# USBJTAG_USBUART_4-Channel.net
KiCad netlist of a schematic drawn in Altium Designer
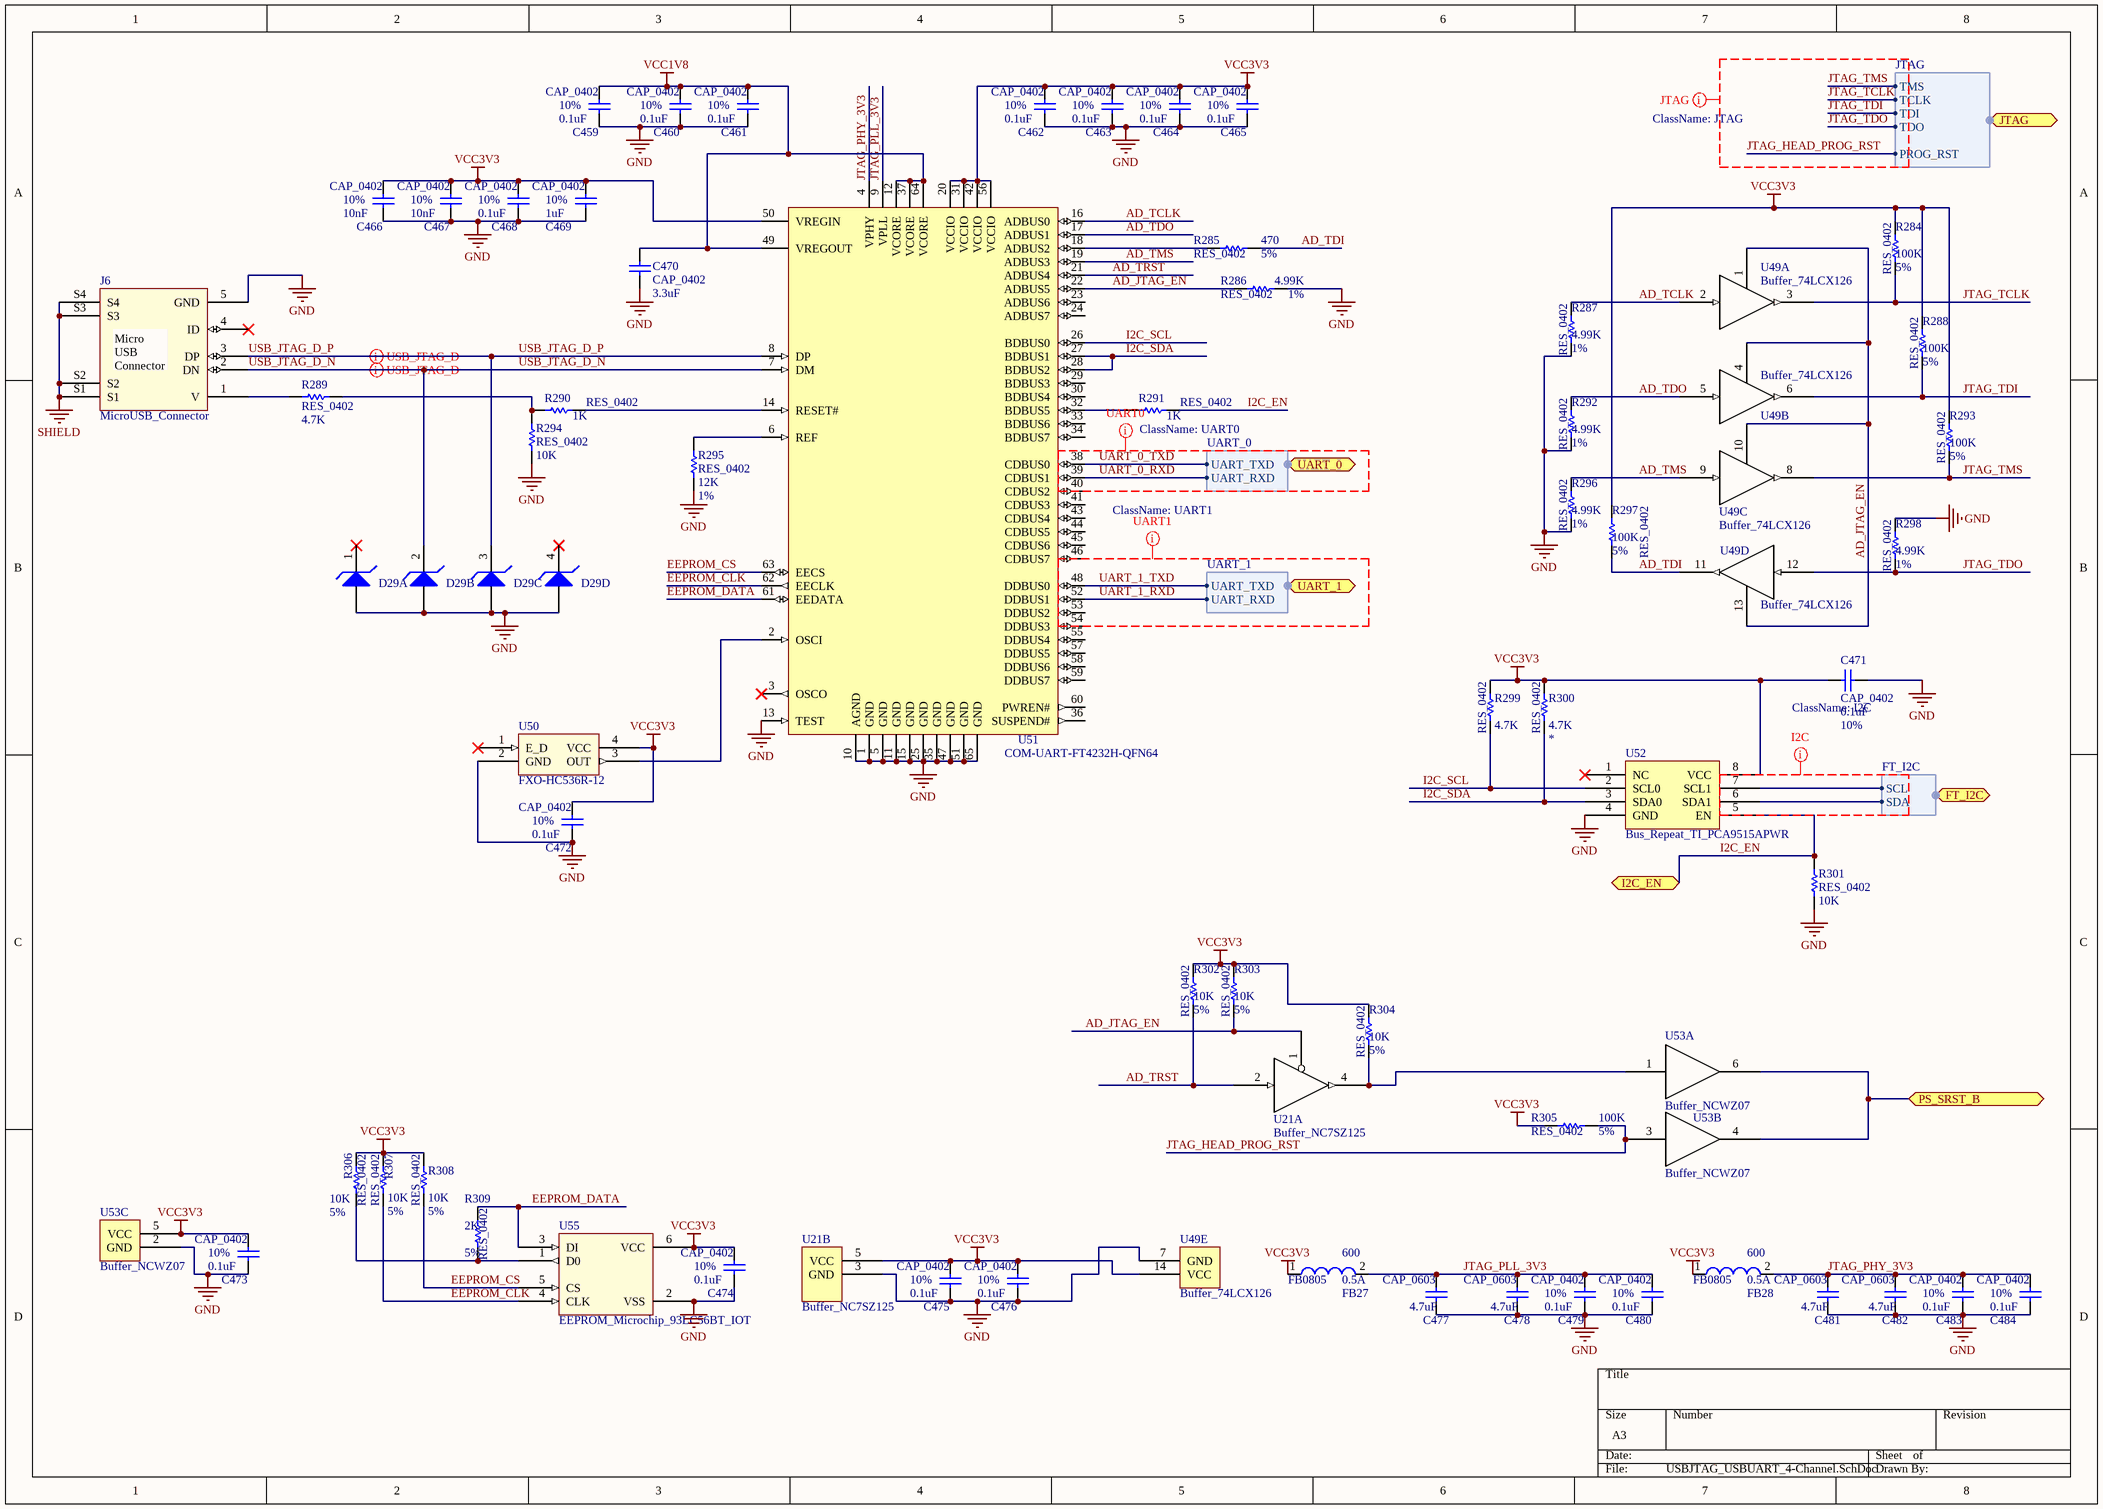
[diagram p0: USBJTAG_USBUART_4-Channel.SchDoc]

(export (version "E")
  (design (tool "Eeschema 10.0.6"))
  (components
    (comp (ref "C459")
      (value "CAP_0402")
      (footprint "CAPC0402(1005)60_N:CAPC0402(1005)60_N")
      (description "0.1uf, ceramic, 10%, 6.3V, X5R, 0402")
      (fields
        (field (name "ALTIUM_VALUE") "0.1uF")
        (field (name "TOLERANCE") "10%")
        (field (name "PART NUMBER") "C1005X5R0J104K")
        (field (name "MANUFACTURER") "TDK Corporation")
      )
      (libsource (lib "COMRAD_Database") (part "CAP_0402"))
    )
    (comp (ref "C460")
      (value "CAP_0402")
      (footprint "CAPC0402(1005)60_N:CAPC0402(1005)60_N")
      (description "0.1uf, ceramic, 10%, 6.3V, X5R, 0402")
      (fields
        (field (name "ALTIUM_VALUE") "0.1uF")
        (field (name "TOLERANCE") "10%")
        (field (name "PART NUMBER") "C1005X5R0J104K")
        (field (name "MANUFACTURER") "TDK Corporation")
      )
      (libsource (lib "COMRAD_Database") (part "CAP_0402"))
    )
    (comp (ref "C461")
      (value "CAP_0402")
      (footprint "CAPC0402(1005)60_N:CAPC0402(1005)60_N")
      (description "0.1uf, ceramic, 10%, 6.3V, X5R, 0402")
      (fields
        (field (name "ALTIUM_VALUE") "0.1uF")
        (field (name "TOLERANCE") "10%")
        (field (name "PART NUMBER") "C1005X5R0J104K")
        (field (name "MANUFACTURER") "TDK Corporation")
      )
      (libsource (lib "COMRAD_Database") (part "CAP_0402"))
    )
    (comp (ref "C462")
      (value "CAP_0402")
      (footprint "CAPC0402(1005)60_N:CAPC0402(1005)60_N")
      (description "0.1uf, ceramic, 10%, 6.3V, X5R, 0402")
      (fields
        (field (name "ALTIUM_VALUE") "0.1uF")
        (field (name "TOLERANCE") "10%")
        (field (name "PART NUMBER") "C1005X5R0J104K")
        (field (name "MANUFACTURER") "TDK Corporation")
      )
      (libsource (lib "COMRAD_Database") (part "CAP_0402"))
    )
    (comp (ref "C463")
      (value "CAP_0402")
      (footprint "CAPC0402(1005)60_N:CAPC0402(1005)60_N")
      (description "0.1uf, ceramic, 10%, 6.3V, X5R, 0402")
      (fields
        (field (name "ALTIUM_VALUE") "0.1uF")
        (field (name "TOLERANCE") "10%")
        (field (name "PART NUMBER") "C1005X5R0J104K")
        (field (name "MANUFACTURER") "TDK Corporation")
      )
      (libsource (lib "COMRAD_Database") (part "CAP_0402"))
    )
    (comp (ref "C464")
      (value "CAP_0402")
      (footprint "CAPC0402(1005)60_N:CAPC0402(1005)60_N")
      (description "0.1uf, ceramic, 10%, 6.3V, X5R, 0402")
      (fields
        (field (name "ALTIUM_VALUE") "0.1uF")
        (field (name "TOLERANCE") "10%")
        (field (name "PART NUMBER") "C1005X5R0J104K")
        (field (name "MANUFACTURER") "TDK Corporation")
      )
      (libsource (lib "COMRAD_Database") (part "CAP_0402"))
    )
    (comp (ref "C465")
      (value "CAP_0402")
      (footprint "CAPC0402(1005)60_N:CAPC0402(1005)60_N")
      (description "0.1uf, ceramic, 10%, 6.3V, X5R, 0402")
      (fields
        (field (name "ALTIUM_VALUE") "0.1uF")
        (field (name "TOLERANCE") "10%")
        (field (name "PART NUMBER") "C1005X5R0J104K")
        (field (name "MANUFACTURER") "TDK Corporation")
      )
      (libsource (lib "COMRAD_Database") (part "CAP_0402"))
    )
    (comp (ref "C466")
      (value "CAP_0402")
      (footprint "CAPC0402(1005)60_N:CAPC0402(1005)60_N")
      (description "10000pF, ceramic, 10% 6.3V X5R, 0402")
      (fields
        (field (name "ALTIUM_VALUE") "10nF")
        (field (name "TOLERANCE") "10%")
        (field (name "PART NUMBER") "GRM155R60J103KA01D")
        (field (name "MANUFACTURER") "Murata Electronics North America")
      )
      (libsource (lib "COMRAD_Database") (part "CAP_0402"))
    )
    (comp (ref "C467")
      (value "CAP_0402")
      (footprint "CAPC0402(1005)60_N:CAPC0402(1005)60_N")
      (description "10000pF, ceramic, 10% 6.3V X5R, 0402")
      (fields
        (field (name "ALTIUM_VALUE") "10nF")
        (field (name "TOLERANCE") "10%")
        (field (name "PART NUMBER") "GRM155R60J103KA01D")
        (field (name "MANUFACTURER") "Murata Electronics North America")
      )
      (libsource (lib "COMRAD_Database") (part "CAP_0402"))
    )
    (comp (ref "C468")
      (value "CAP_0402")
      (footprint "CAPC0402(1005)60_N:CAPC0402(1005)60_N")
      (description "0.1uf, ceramic, 10%, 6.3V, X5R, 0402")
      (fields
        (field (name "ALTIUM_VALUE") "0.1uF")
        (field (name "TOLERANCE") "10%")
        (field (name "PART NUMBER") "C1005X5R0J104K")
        (field (name "MANUFACTURER") "TDK Corporation")
      )
      (libsource (lib "COMRAD_Database") (part "CAP_0402"))
    )
    (comp (ref "C469")
      (value "CAP_0402")
      (footprint "CAPC0402(1005)60_N:CAPC0402(1005)60_N")
      (description "1uF, ceramic, 10%, 6.3V, X5R, 0402")
      (fields
        (field (name "ALTIUM_VALUE") "1uF")
        (field (name "TOLERANCE") "10%")
        (field (name "PART NUMBER") "C1005X5R0J105K")
        (field (name "MANUFACTURER") "TDK Corporation")
      )
      (libsource (lib "COMRAD_Database") (part "CAP_0402"))
    )
    (comp (ref "C470")
      (value "CAP_0402")
      (footprint "CAPC0402(1005)60_N")
      (description "CAP CER 3.3UF 6.3V 20% X5R 0402")
      (fields
        (field (name "ALTIUM_VALUE") "3.3uF")
        (field (name "TOLERANCE") "20%")
        (field (name "PART NUMBER") "C1005X5R0J335M050BC")
      )
      (libsource (lib "COMRAD_Database") (part "CAP_0402"))
    )
    (comp (ref "C471")
      (value "CAP_0402")
      (footprint "CAPC0402(1005)60_N:CAPC0402(1005)60_N")
      (description "0.1uf, ceramic, 10%, 6.3V, X5R, 0402")
      (fields
        (field (name "ALTIUM_VALUE") "0.1uF")
        (field (name "TOLERANCE") "10%")
        (field (name "PART NUMBER") "C1005X5R0J104K")
        (field (name "MANUFACTURER") "TDK Corporation")
      )
      (libsource (lib "COMRAD_Database") (part "CAP_0402"))
    )
    (comp (ref "C472")
      (value "CAP_0402")
      (footprint "CAPC0402(1005)60_N:CAPC0402(1005)60_N")
      (description "0.1uf, ceramic, 10%, 6.3V, X5R, 0402")
      (fields
        (field (name "ALTIUM_VALUE") "0.1uF")
        (field (name "TOLERANCE") "10%")
        (field (name "PART NUMBER") "C1005X5R0J104K")
        (field (name "MANUFACTURER") "TDK Corporation")
      )
      (libsource (lib "COMRAD_Database") (part "CAP_0402"))
    )
    (comp (ref "C473")
      (value "CAP_0402")
      (footprint "CAPC0402(1005)60_N:CAPC0402(1005)60_N")
      (description "0.1uf, ceramic, 10%, 6.3V, X5R, 0402")
      (fields
        (field (name "ALTIUM_VALUE") "0.1uF")
        (field (name "TOLERANCE") "10%")
        (field (name "PART NUMBER") "C1005X5R0J104K")
        (field (name "MANUFACTURER") "TDK Corporation")
      )
      (libsource (lib "COMRAD_Database") (part "CAP_0402"))
    )
    (comp (ref "C474")
      (value "CAP_0402")
      (footprint "CAPC0402(1005)60_N:CAPC0402(1005)60_N")
      (description "0.1uf, ceramic, 10%, 6.3V, X5R, 0402")
      (fields
        (field (name "ALTIUM_VALUE") "0.1uF")
        (field (name "TOLERANCE") "10%")
        (field (name "PART NUMBER") "C1005X5R0J104K")
        (field (name "MANUFACTURER") "TDK Corporation")
      )
      (libsource (lib "COMRAD_Database") (part "CAP_0402"))
    )
    (comp (ref "C475")
      (value "CAP_0402")
      (footprint "CAPC0402(1005)60_N:CAPC0402(1005)60_N")
      (description "0.1uf, ceramic, 10%, 6.3V, X5R, 0402")
      (fields
        (field (name "ALTIUM_VALUE") "0.1uF")
        (field (name "TOLERANCE") "10%")
        (field (name "PART NUMBER") "C1005X5R0J104K")
        (field (name "MANUFACTURER") "TDK Corporation")
      )
      (libsource (lib "COMRAD_Database") (part "CAP_0402"))
    )
    (comp (ref "C476")
      (value "CAP_0402")
      (footprint "CAPC0402(1005)60_N:CAPC0402(1005)60_N")
      (description "0.1uf, ceramic, 10%, 6.3V, X5R, 0402")
      (fields
        (field (name "ALTIUM_VALUE") "0.1uF")
        (field (name "TOLERANCE") "10%")
        (field (name "PART NUMBER") "C1005X5R0J104K")
        (field (name "MANUFACTURER") "TDK Corporation")
      )
      (libsource (lib "COMRAD_Database") (part "CAP_0402"))
    )
    (comp (ref "C477")
      (value "CAP_0603")
      (footprint "CAPC0603(1608)100_N")
      (description "4.7uF, ceramic, 10%, 10V X5R, 0603")
      (fields
        (field (name "ALTIUM_VALUE") "4.7uF")
        (field (name "TOLERANCE") "10%")
        (field (name "PART NUMBER") "LMK107BJ475KA-T")
      )
      (libsource (lib "COMRAD_Database") (part "CAP_0603"))
    )
    (comp (ref "C478")
      (value "CAP_0603")
      (footprint "CAPC0603(1608)100_N")
      (description "4.7uF, ceramic, 10%, 10V X5R, 0603")
      (fields
        (field (name "ALTIUM_VALUE") "4.7uF")
        (field (name "TOLERANCE") "10%")
        (field (name "PART NUMBER") "LMK107BJ475KA-T")
      )
      (libsource (lib "COMRAD_Database") (part "CAP_0603"))
    )
    (comp (ref "C479")
      (value "CAP_0402")
      (footprint "CAPC0402(1005)60_N:CAPC0402(1005)60_N")
      (description "0.1uf, ceramic, 10%, 6.3V, X5R, 0402")
      (fields
        (field (name "ALTIUM_VALUE") "0.1uF")
        (field (name "TOLERANCE") "10%")
        (field (name "PART NUMBER") "C1005X5R0J104K")
        (field (name "MANUFACTURER") "TDK Corporation")
      )
      (libsource (lib "COMRAD_Database") (part "CAP_0402"))
    )
    (comp (ref "C480")
      (value "CAP_0402")
      (footprint "CAPC0402(1005)60_N:CAPC0402(1005)60_N")
      (description "0.1uf, ceramic, 10%, 6.3V, X5R, 0402")
      (fields
        (field (name "ALTIUM_VALUE") "0.1uF")
        (field (name "TOLERANCE") "10%")
        (field (name "PART NUMBER") "C1005X5R0J104K")
        (field (name "MANUFACTURER") "TDK Corporation")
      )
      (libsource (lib "COMRAD_Database") (part "CAP_0402"))
    )
    (comp (ref "C481")
      (value "CAP_0603")
      (footprint "CAPC0603(1608)100_N")
      (description "4.7uF, ceramic, 10%, 10V X5R, 0603")
      (fields
        (field (name "ALTIUM_VALUE") "4.7uF")
        (field (name "TOLERANCE") "10%")
        (field (name "PART NUMBER") "LMK107BJ475KA-T")
      )
      (libsource (lib "COMRAD_Database") (part "CAP_0603"))
    )
    (comp (ref "C482")
      (value "CAP_0603")
      (footprint "CAPC0603(1608)100_N")
      (description "4.7uF, ceramic, 10%, 10V X5R, 0603")
      (fields
        (field (name "ALTIUM_VALUE") "4.7uF")
        (field (name "TOLERANCE") "10%")
        (field (name "PART NUMBER") "LMK107BJ475KA-T")
      )
      (libsource (lib "COMRAD_Database") (part "CAP_0603"))
    )
    (comp (ref "C483")
      (value "CAP_0402")
      (footprint "CAPC0402(1005)60_N:CAPC0402(1005)60_N")
      (description "0.1uf, ceramic, 10%, 6.3V, X5R, 0402")
      (fields
        (field (name "ALTIUM_VALUE") "0.1uF")
        (field (name "TOLERANCE") "10%")
        (field (name "PART NUMBER") "C1005X5R0J104K")
        (field (name "MANUFACTURER") "TDK Corporation")
      )
      (libsource (lib "COMRAD_Database") (part "CAP_0402"))
    )
    (comp (ref "C484")
      (value "CAP_0402")
      (footprint "CAPC0402(1005)60_N:CAPC0402(1005)60_N")
      (description "0.1uf, ceramic, 10%, 6.3V, X5R, 0402")
      (fields
        (field (name "ALTIUM_VALUE") "0.1uF")
        (field (name "TOLERANCE") "10%")
        (field (name "PART NUMBER") "C1005X5R0J104K")
        (field (name "MANUFACTURER") "TDK Corporation")
      )
      (libsource (lib "COMRAD_Database") (part "CAP_0402"))
    )
    (comp (ref "D29")
      (value "QuadESDDiode_TEConnectivity_SESD0802Q4UG")
      (footprint "QuadESDDiode_TEConnectivity_SESD0802Q4UG_5-PIN")
      (description "SESD0802Q4UG, Quad Diode Array for ESD protection")
      (fields (field (name "PART NUMBER") "RF2197-000") (field (name "MANUFACTURER") "TE Connectivity"))
      (libsource (lib "COMRAD_Database") (part "QuadESDDiode_TEConnectivity_SESD0802Q4UG"))
    )
    (comp (ref "FB27")
      (value "FB0805")
      (footprint "Inductor0805(2012)")
      (description "MPZ2012S601A, 600 ohm, 100MHz, 0805")
      (fields
        (field (name "RESISTANCE") "600")
        (field (name "MAX_CURRENT") "0.5A")
        (field (name "PART NUMBER") "MPZ2012S601A")
        (field (name "MANUFACTURER") "TDK Corporation")
      )
      (libsource (lib "COMRAD_Database") (part "FerriteBead0805"))
    )
    (comp (ref "FB28")
      (value "FB0805")
      (footprint "Inductor0805(2012)")
      (description "MPZ2012S601A, 600 ohm, 100MHz, 0805")
      (fields
        (field (name "RESISTANCE") "600")
        (field (name "MAX_CURRENT") "0.5A")
        (field (name "PART NUMBER") "MPZ2012S601A")
        (field (name "MANUFACTURER") "TDK Corporation")
      )
      (libsource (lib "COMRAD_Database") (part "FerriteBead0805"))
    )
    (comp (ref "J6")
      (value "MicroUSB_Connector")
      (footprint "MicroUSB_ConnReceptacle_Hirose_ZX62-B-5PA(11)_pcb")
      (description "CONN RCPT MICRO USB B SMD R/A")
      (fields
        (field (name "PART NUMBER") "ZX62-B-5PA(11)")
        (field (name "MANUFACTURER") "Hirose Electric Co Ltd")
      )
      (libsource (lib "COMRAD_Database") (part "MicroUSB_Connector"))
    )
    (comp (ref "R284")
      (value "RES_0402")
      (footprint "RESC0402(1005)_N:RESC0402(1005)_N")
      (description "100K ohm, 5%, 1/16W, 0402")
      (fields
        (field (name "ALTIUM_VALUE") "100K")
        (field (name "TOLERANCE") "5%")
        (field (name "PART NUMBER") "RC0402JR-07100KL")
        (field (name "MANUFACTURER") "Yageo America")
      )
      (libsource (lib "COMRAD_Database") (part "RES_0402"))
    )
    (comp (ref "R285")
      (value "RES_0402")
      (footprint "RESC0402(1005)_N:RESC0402(1005)_N")
      (description "470 ohm, 5%, 1/16W, 0402")
      (fields
        (field (name "ALTIUM_VALUE") "470")
        (field (name "TOLERANCE") "5%")
        (field (name "PART NUMBER") "MCR01MZPJ471")
        (field (name "MANUFACTURER") "ROHM")
      )
      (libsource (lib "COMRAD_Database") (part "RES_0402"))
    )
    (comp (ref "R286")
      (value "RES_0402")
      (footprint "RESC0402(1005)_N:RESC0402(1005)_N")
      (description "4.99K ohm, 1% 1/16W, 0402")
      (fields
        (field (name "ALTIUM_VALUE") "4.99K")
        (field (name "TOLERANCE") "1%")
        (field (name "PART NUMBER") "CRCW04024K99FKED")
        (field (name "MANUFACTURER") "Vishay/Dale")
      )
      (libsource (lib "COMRAD_Database") (part "RES_0402"))
    )
    (comp (ref "R287")
      (value "RES_0402")
      (footprint "RESC0402(1005)_N:RESC0402(1005)_N")
      (description "4.99K ohm, 1% 1/16W, 0402")
      (fields
        (field (name "ALTIUM_VALUE") "4.99K")
        (field (name "TOLERANCE") "1%")
        (field (name "PART NUMBER") "CRCW04024K99FKED")
        (field (name "MANUFACTURER") "Vishay/Dale")
      )
      (libsource (lib "COMRAD_Database") (part "RES_0402"))
    )
    (comp (ref "R288")
      (value "RES_0402")
      (footprint "RESC0402(1005)_N:RESC0402(1005)_N")
      (description "100K ohm, 5%, 1/16W, 0402")
      (fields
        (field (name "ALTIUM_VALUE") "100K")
        (field (name "TOLERANCE") "5%")
        (field (name "PART NUMBER") "RC0402JR-07100KL")
        (field (name "MANUFACTURER") "Yageo America")
      )
      (libsource (lib "COMRAD_Database") (part "RES_0402"))
    )
    (comp (ref "R289")
      (value "RES_0402")
      (footprint "RESC0402(1005)_N")
      (description "4.7K ohm, 5%, 1/16W, 0402")
      (fields
        (field (name "ALTIUM_VALUE") "4.7K")
        (field (name "TOLERANCE") "5%")
        (field (name "PART NUMBER") "RC0402JR-074K7L")
      )
      (libsource (lib "COMRAD_Database") (part "RES_0402"))
    )
    (comp (ref "R290")
      (value "RES_0402")
      (footprint "RESC0402(1005)_N")
      (description "1K ohm, 5%, 1/16W, 0402")
      (fields
        (field (name "ALTIUM_VALUE") "1K")
        (field (name "TOLERANCE") "5%")
        (field (name "PART NUMBER") "RC0402JR-071KL")
      )
      (libsource (lib "COMRAD_Database") (part "RES_0402"))
    )
    (comp (ref "R291")
      (value "RES_0402")
      (footprint "RESC0402(1005)_N")
      (description "1K ohm, 5%, 1/16W, 0402")
      (fields
        (field (name "ALTIUM_VALUE") "1K")
        (field (name "TOLERANCE") "5%")
        (field (name "PART NUMBER") "RC0402JR-071KL")
      )
      (libsource (lib "COMRAD_Database") (part "RES_0402"))
    )
    (comp (ref "R292")
      (value "RES_0402")
      (footprint "RESC0402(1005)_N:RESC0402(1005)_N")
      (description "4.99K ohm, 1% 1/16W, 0402")
      (fields
        (field (name "ALTIUM_VALUE") "4.99K")
        (field (name "TOLERANCE") "1%")
        (field (name "PART NUMBER") "CRCW04024K99FKED")
        (field (name "MANUFACTURER") "Vishay/Dale")
      )
      (libsource (lib "COMRAD_Database") (part "RES_0402"))
    )
    (comp (ref "R293")
      (value "RES_0402")
      (footprint "RESC0402(1005)_N:RESC0402(1005)_N")
      (description "100K ohm, 5%, 1/16W, 0402")
      (fields
        (field (name "ALTIUM_VALUE") "100K")
        (field (name "TOLERANCE") "5%")
        (field (name "PART NUMBER") "RC0402JR-07100KL")
        (field (name "MANUFACTURER") "Yageo America")
      )
      (libsource (lib "COMRAD_Database") (part "RES_0402"))
    )
    (comp (ref "R294")
      (value "RES_0402")
      (footprint "RESC0402(1005)_N")
      (description "10K ohm, 5%, 1/16W, 0402")
      (fields
        (field (name "ALTIUM_VALUE") "10K")
        (field (name "TOLERANCE") "5%")
        (field (name "PART NUMBER") "RC0402JR-0710KL")
      )
      (libsource (lib "COMRAD_Database") (part "RES_0402"))
    )
    (comp (ref "R295")
      (value "RES_0402")
      (footprint "RESC0402(1005)_N:RESC0402(1005)_N")
      (description "12K ohm, 1% 1/10W, 0402")
      (fields
        (field (name "ALTIUM_VALUE") "12K")
        (field (name "TOLERANCE") "1%")
        (field (name "PART NUMBER") "ERJ-2RKF1202X")
        (field (name "MANUFACTURER") "Panasonic - ECG")
      )
      (libsource (lib "COMRAD_Database") (part "RES_0402"))
    )
    (comp (ref "R296")
      (value "RES_0402")
      (footprint "RESC0402(1005)_N:RESC0402(1005)_N")
      (description "4.99K ohm, 1% 1/16W, 0402")
      (fields
        (field (name "ALTIUM_VALUE") "4.99K")
        (field (name "TOLERANCE") "1%")
        (field (name "PART NUMBER") "CRCW04024K99FKED")
        (field (name "MANUFACTURER") "Vishay/Dale")
      )
      (libsource (lib "COMRAD_Database") (part "RES_0402"))
    )
    (comp (ref "R297")
      (value "RES_0402")
      (footprint "RESC0402(1005)_N:RESC0402(1005)_N")
      (description "100K ohm, 5%, 1/16W, 0402")
      (fields
        (field (name "ALTIUM_VALUE") "100K")
        (field (name "TOLERANCE") "5%")
        (field (name "PART NUMBER") "RC0402JR-07100KL")
        (field (name "MANUFACTURER") "Yageo America")
      )
      (libsource (lib "COMRAD_Database") (part "RES_0402"))
    )
    (comp (ref "R298")
      (value "RES_0402")
      (footprint "RESC0402(1005)_N:RESC0402(1005)_N")
      (description "4.99K ohm, 1% 1/16W, 0402")
      (fields
        (field (name "ALTIUM_VALUE") "4.99K")
        (field (name "TOLERANCE") "1%")
        (field (name "PART NUMBER") "CRCW04024K99FKED")
        (field (name "MANUFACTURER") "Vishay/Dale")
      )
      (libsource (lib "COMRAD_Database") (part "RES_0402"))
    )
    (comp (ref "R299")
      (value "RES_0402")
      (footprint "RESC0402(1005)_N")
      (description "4.7K ohm, 5%, 1/16W, 0402")
      (fields
        (field (name "ALTIUM_VALUE") "4.7K")
        (field (name "TOLERANCE") "5%")
        (field (name "PART NUMBER") "RC0402JR-074K7L")
      )
      (libsource (lib "COMRAD_Database") (part "RES_0402"))
    )
    (comp (ref "R300")
      (value "RES_0402")
      (footprint "RESC0402(1005)_N")
      (description "4.7K ohm, 5%, 1/16W, 0402")
      (fields
        (field (name "ALTIUM_VALUE") "4.7K")
        (field (name "TOLERANCE") "*")
        (field (name "PART NUMBER") "RC0402JR-074K7L")
        (field (name "MANUFACTURER") "Yageo America")
      )
      (libsource (lib "COMRAD_Database") (part "RES_0402"))
    )
    (comp (ref "R301")
      (value "RES_0402")
      (footprint "RESC0402(1005)_N")
      (description "10K ohm, 5%, 1/16W, 0402")
      (fields
        (field (name "ALTIUM_VALUE") "10K")
        (field (name "TOLERANCE") "5%")
        (field (name "PART NUMBER") "RC0402JR-0710KL")
      )
      (libsource (lib "COMRAD_Database") (part "RES_0402"))
    )
    (comp (ref "R302")
      (value "RES_0402")
      (footprint "RESC0402(1005)_N:RESC0402(1005)_N")
      (description "10K ohm, 5%, 1/16W, 0402")
      (fields
        (field (name "ALTIUM_VALUE") "10K")
        (field (name "TOLERANCE") "5%")
        (field (name "PART NUMBER") "RC0402JR-0710KL")
        (field (name "MANUFACTURER") "Yageo America")
      )
      (libsource (lib "COMRAD_Database") (part "RES_0402"))
    )
    (comp (ref "R303")
      (value "RES_0402")
      (footprint "RESC0402(1005)_N:RESC0402(1005)_N")
      (description "10K ohm, 5%, 1/16W, 0402")
      (fields
        (field (name "ALTIUM_VALUE") "10K")
        (field (name "TOLERANCE") "5%")
        (field (name "PART NUMBER") "RC0402JR-0710KL")
        (field (name "MANUFACTURER") "Yageo America")
      )
      (libsource (lib "COMRAD_Database") (part "RES_0402"))
    )
    (comp (ref "R304")
      (value "RES_0402")
      (footprint "RESC0402(1005)_N:RESC0402(1005)_N")
      (description "10K ohm, 5%, 1/16W, 0402")
      (fields
        (field (name "ALTIUM_VALUE") "10K")
        (field (name "TOLERANCE") "5%")
        (field (name "PART NUMBER") "RC0402JR-0710KL")
        (field (name "MANUFACTURER") "Yageo America")
      )
      (libsource (lib "COMRAD_Database") (part "RES_0402"))
    )
    (comp (ref "R305")
      (value "RES_0402")
      (footprint "RESC0402(1005)_N:RESC0402(1005)_N")
      (description "100K ohm, 5%, 1/16W, 0402")
      (fields
        (field (name "ALTIUM_VALUE") "100K")
        (field (name "TOLERANCE") "5%")
        (field (name "PART NUMBER") "RC0402JR-07100KL")
        (field (name "MANUFACTURER") "Yageo America")
      )
      (libsource (lib "COMRAD_Database") (part "RES_0402"))
    )
    (comp (ref "R306")
      (value "RES_0402")
      (footprint "RESC0402(1005)_N:RESC0402(1005)_N")
      (description "10K ohm, 5%, 1/16W, 0402")
      (fields
        (field (name "ALTIUM_VALUE") "10K")
        (field (name "TOLERANCE") "5%")
        (field (name "PART NUMBER") "RC0402JR-0710KL")
        (field (name "MANUFACTURER") "Yageo America")
      )
      (libsource (lib "COMRAD_Database") (part "RES_0402"))
    )
    (comp (ref "R307")
      (value "RES_0402")
      (footprint "RESC0402(1005)_N:RESC0402(1005)_N")
      (description "10K ohm, 5%, 1/16W, 0402")
      (fields
        (field (name "ALTIUM_VALUE") "10K")
        (field (name "TOLERANCE") "5%")
        (field (name "PART NUMBER") "RC0402JR-0710KL")
        (field (name "MANUFACTURER") "Yageo America")
      )
      (libsource (lib "COMRAD_Database") (part "RES_0402"))
    )
    (comp (ref "R308")
      (value "RES_0402")
      (footprint "RESC0402(1005)_N:RESC0402(1005)_N")
      (description "10K ohm, 5%, 1/16W, 0402")
      (fields
        (field (name "ALTIUM_VALUE") "10K")
        (field (name "TOLERANCE") "5%")
        (field (name "PART NUMBER") "RC0402JR-0710KL")
        (field (name "MANUFACTURER") "Yageo America")
      )
      (libsource (lib "COMRAD_Database") (part "RES_0402"))
    )
    (comp (ref "R309")
      (value "RES_0402")
      (footprint "RESC0402(1005)_N:RESC0402(1005)_N")
      (description "2K ohm, 5% 1/16W, 0402")
      (fields
        (field (name "ALTIUM_VALUE") "2K")
        (field (name "TOLERANCE") "5%")
        (field (name "PART NUMBER") "ERJ-2GEJ202X")
        (field (name "MANUFACTURER") "Panasonic - ECG")
      )
      (libsource (lib "COMRAD_Database") (part "RES_0402"))
    )
    (comp (ref "U21")
      (value "Buffer_NC7SZ125")
      (footprint "Buffer_Fairchild_NC7SZ125_SOT95P280X145-5N")
      (description "NC7SZ125M5X, Tri-State Buffer UHS, SOT-23")
      (fields
        (field (name "PART NUMBER") "NC7SZ125M5X")
        (field (name "MANUFACTURER") "FAIRCHILD SEMICONDUCTOR")
      )
      (libsource (lib "COMRAD_Database") (part "Buffer_Fairchild_NC7SZ125"))
    )
    (comp (ref "U49")
      (value "Buffer_74LCX126")
      (footprint "Buffer_Fairchild_74LCX126_DQFN-14")
      (description "74LCX126BQX, quad buffer, LV N-Inv, DQFN14")
      (fields
        (field (name "PART NUMBER") "74LCX126BQX")
        (field (name "MANUFACTURER") "FAIRCHILD SEMICONDUCTOR")
      )
      (libsource (lib "COMRAD_Database") (part "Buffer_74LCX126"))
    )
    (comp (ref "U50")
      (value "FXO-HC536R-12")
      (footprint "Oscillator_Fox_767-12-69_HC5")
      (description "767-12-69, 12MHz 3.3V HCMOS Oscillator, HC5")
      (fields (field (name "MANUFACTURER") "Fox Electronics"))
      (libsource (lib "COMRAD_Database") (part "Oscillator_Fox_767-12-69"))
    )
    (comp (ref "U51")
      (value "COM-UART-FT4232H-QFN64")
      (footprint "FTDI_FT4232HQ_QFN64_2_N")
      (description "IC USB HS QUAD UART/SYNC 64-QFN")
      (fields
        (field (name "PART NUMBER") "FT4232HQ-REEL")
        (field (name "MANUFACTURER") "FTDI, Future Technology Devices International Ltd")
      )
      (libsource (lib "COMRAD_Database") (part "COM-UART-FT4232H-QFN64"))
    )
    (comp (ref "U52")
      (value "Bus_Repeat_TI_PCA9515APWR")
      (footprint "Bus_Repeat_TI_PCA9515APWR_8-TSSOP")
      (description "IC DUAL BIDIR BUS REPEAT 8-TSSOP")
      (fields (field (name "PART NUMBER") "PCA9515APWR") (field (name "MANUFACTURER") "Texas Instruments"))
      (libsource (lib "COMRAD_Database") (part "Bus_Repeat_TI_PCA9515APWR"))
    )
    (comp (ref "U53")
      (value "Buffer_NCWZ07")
      (footprint "Buffer_Fairchild_NCWZ07_SC70-6")
      (description "NC7WZ07, dual non-inverting buffer, SC-70-6 (SOT-363)")
      (fields
        (field (name "PART NUMBER") "NC7WZ07P6X")
        (field (name "MANUFACTURER") "FAIRCHILD OPTOELECTRICS GROUP")
      )
      (libsource (lib "COMRAD_Database") (part "Buffer_Fairchild_NCWZ07"))
    )
    (comp (ref "U55")
      (value "EEPROM_Microchip_93LC56BT_IOT")
      (footprint "EEPROM_Microchip_93LC56BT_IOT_SOT23-6")
      (description "93LC56BT-I/OT, EEPROM 2Kbit 3MHz, SOT23-6")
      (fields
        (field (name "PART NUMBER") "93LC56BT-I/OT")
        (field (name "MANUFACTURER") "Microchip Technology")
      )
      (libsource (lib "COMRAD_Database") (part "EEPROM_Microchip_93LC56BT_IOT"))
    )
  )
  (nets
    (net (code "5") (name "/AD_JTAG_EN") (class "Default")
      (node (ref "R286") (pin "1") (pinfunction "1_1") (pintype "passive"))
      (node (ref "R303") (pin "1") (pinfunction "1_1") (pintype "passive"))
      (node (ref "U21") (pin "1") (pintype "passive"))
      (node (ref "U49") (pin "1") (pintype "passive"))
      (node (ref "U49") (pin "10") (pintype "passive"))
      (node (ref "U49") (pin "13") (pintype "passive"))
      (node (ref "U49") (pin "4") (pintype "passive"))
      (node (ref "U51") (pin "22") (pinfunction "ADBUS5_22") (pintype "bidirectional"))
    )
    (net (code "6") (name "/AD_TCLK") (class "Default")
      (node (ref "R287") (pin "2") (pinfunction "2_2") (pintype "passive"))
      (node (ref "U49") (pin "2") (pintype "input"))
      (node (ref "U51") (pin "16") (pinfunction "ADBUS0_16") (pintype "bidirectional"))
    )
    (net (code "7") (name "/AD_TDI") (class "Default")
      (node (ref "R285") (pin "2") (pinfunction "2_2") (pintype "passive"))
      (node (ref "R297") (pin "1") (pinfunction "1_1") (pintype "passive"))
      (node (ref "U49") (pin "11") (pintype "output"))
    )
    (net (code "8") (name "/AD_TDO") (class "Default")
      (node (ref "R292") (pin "2") (pinfunction "2_2") (pintype "passive"))
      (node (ref "U49") (pin "5") (pintype "input"))
      (node (ref "U51") (pin "17") (pinfunction "ADBUS1_17") (pintype "bidirectional"))
    )
    (net (code "9") (name "/AD_TMS") (class "Default")
      (node (ref "R296") (pin "2") (pinfunction "2_2") (pintype "passive"))
      (node (ref "U49") (pin "9") (pintype "input"))
      (node (ref "U51") (pin "19") (pinfunction "ADBUS3_19") (pintype "bidirectional"))
    )
    (net (code "10") (name "/AD_TRST") (class "Default")
      (node (ref "R302") (pin "1") (pinfunction "1_1") (pintype "passive"))
      (node (ref "U21") (pin "2") (pintype "input"))
      (node (ref "U51") (pin "21") (pinfunction "ADBUS4_21") (pintype "bidirectional"))
    )
    (net (code "11") (name "/EEPROM_CLK") (class "Default")
      (node (ref "R307") (pin "1") (pinfunction "1_1") (pintype "passive"))
      (node (ref "U51") (pin "62") (pinfunction "EECLK_62") (pintype "output"))
      (node (ref "U55") (pin "4") (pinfunction "CLK_4") (pintype "input"))
    )
    (net (code "12") (name "/EEPROM_CS") (class "Default")
      (node (ref "R308") (pin "1") (pinfunction "1_1") (pintype "passive"))
      (node (ref "U51") (pin "63") (pinfunction "EECS_63") (pintype "bidirectional"))
      (node (ref "U55") (pin "5") (pinfunction "CS_5") (pintype "input"))
    )
    (net (code "13") (name "/EEPROM_DATA") (class "Default")
      (node (ref "R309") (pin "2") (pinfunction "2_2") (pintype "passive"))
      (node (ref "U51") (pin "61") (pinfunction "EEDATA_61") (pintype "bidirectional"))
      (node (ref "U55") (pin "3") (pinfunction "DI_3") (pintype "input"))
    )
    (net (code "14") (name "/I2C_EN") (class "Default")
      (node (ref "R291") (pin "2") (pinfunction "2_2") (pintype "passive"))
      (node (ref "R301") (pin "2") (pinfunction "2_2") (pintype "passive"))
      (node (ref "U52") (pin "5") (pinfunction "EN_5") (pintype "passive"))
    )
    (net (code "15") (name "/I2C_SCL") (class "Default")
      (node (ref "R299") (pin "1") (pinfunction "1_1") (pintype "passive"))
      (node (ref "U51") (pin "26") (pinfunction "BDBUS0_26") (pintype "bidirectional"))
      (node (ref "U52") (pin "2") (pinfunction "SCL0_2") (pintype "passive"))
    )
    (net (code "16") (name "/I2C_SDA") (class "Default")
      (node (ref "R300") (pin "1") (pinfunction "1_1") (pintype "passive"))
      (node (ref "U51") (pin "27") (pinfunction "BDBUS1_27") (pintype "bidirectional"))
      (node (ref "U51") (pin "28") (pinfunction "BDBUS2_28") (pintype "bidirectional"))
      (node (ref "U52") (pin "3") (pinfunction "SDA0_3") (pintype "passive"))
    )
    (net (code "17") (name "/JTAG_HEAD_PROG_RST") (class "Default")
      (node (ref "R305") (pin "1") (pinfunction "1_1") (pintype "passive"))
      (node (ref "U53") (pin "3") (pintype "passive"))
    )
    (net (code "18") (name "/JTAG_PHY_3V3") (class "Default")
      (node (ref "C481") (pin "2") (pinfunction "2_2") (pintype "passive"))
      (node (ref "C482") (pin "2") (pinfunction "2_2") (pintype "passive"))
      (node (ref "C483") (pin "2") (pinfunction "2_2") (pintype "passive"))
      (node (ref "C484") (pin "2") (pinfunction "2_2") (pintype "passive"))
      (node (ref "FB28") (pin "2") (pinfunction "2_2") (pintype "passive"))
      (node (ref "U51") (pin "4") (pinfunction "VPHY_4") (pintype "power_in"))
    )
    (net (code "19") (name "/JTAG_PLL_3V3") (class "Default")
      (node (ref "C477") (pin "2") (pinfunction "2_2") (pintype "passive"))
      (node (ref "C478") (pin "2") (pinfunction "2_2") (pintype "passive"))
      (node (ref "C479") (pin "2") (pinfunction "2_2") (pintype "passive"))
      (node (ref "C480") (pin "2") (pinfunction "2_2") (pintype "passive"))
      (node (ref "FB27") (pin "2") (pinfunction "2_2") (pintype "passive"))
      (node (ref "U51") (pin "9") (pinfunction "VPLL_9") (pintype "power_in"))
    )
    (net (code "20") (name "/JTAG_TCLK") (class "Default")
      (node (ref "R284") (pin "1") (pinfunction "1_1") (pintype "passive"))
      (node (ref "U49") (pin "3") (pintype "output"))
    )
    (net (code "21") (name "/JTAG_TDI") (class "Default")
      (node (ref "R288") (pin "1") (pinfunction "1_1") (pintype "passive"))
      (node (ref "U49") (pin "6") (pintype "output"))
    )
    (net (code "22") (name "/JTAG_TDO") (class "Default")
      (node (ref "R298") (pin "1") (pinfunction "1_1") (pintype "passive"))
      (node (ref "U49") (pin "12") (pintype "input"))
    )
    (net (code "23") (name "/JTAG_TMS") (class "Default")
      (node (ref "R293") (pin "1") (pinfunction "1_1") (pintype "passive"))
      (node (ref "U49") (pin "8") (pintype "output"))
    )
    (net (code "24") (name "/PS_SRST_B") (class "Default")
      (node (ref "U53") (pin "4") (pintype "passive"))
      (node (ref "U53") (pin "6") (pintype "passive"))
    )
    (net (code "25") (name "/SCL") (class "Default")
      (node (ref "U52") (pin "7") (pinfunction "SCL1_7") (pintype "passive"))
    )
    (net (code "26") (name "/SDA") (class "Default")
      (node (ref "U52") (pin "6") (pinfunction "SDA1_6") (pintype "passive"))
    )
    (net (code "27") (name "/UART_0_RXD") (class "Default")
      (node (ref "U51") (pin "39") (pinfunction "CDBUS1_39") (pintype "bidirectional"))
    )
    (net (code "28") (name "/UART_0_TXD") (class "Default")
      (node (ref "U51") (pin "38") (pinfunction "CDBUS0_38") (pintype "bidirectional"))
    )
    (net (code "29") (name "/UART_1_RXD") (class "Default")
      (node (ref "U51") (pin "52") (pinfunction "DDBUS1_52") (pintype "bidirectional"))
    )
    (net (code "30") (name "/UART_1_TXD") (class "Default")
      (node (ref "U51") (pin "48") (pinfunction "DDBUS0_48") (pintype "bidirectional"))
    )
    (net (code "31") (name "/USB_JTAG_D_N") (class "Default")
      (node (ref "D29") (pin "2") (pinfunction "K_2") (pintype "passive"))
      (node (ref "J6") (pin "2") (pinfunction "DN_2") (pintype "bidirectional"))
      (node (ref "U51") (pin "7") (pinfunction "DM_7") (pintype "input"))
    )
    (net (code "32") (name "/USB_JTAG_D_P") (class "Default")
      (node (ref "D29") (pin "3") (pinfunction "K_3") (pintype "passive"))
      (node (ref "J6") (pin "3") (pinfunction "DP_3") (pintype "bidirectional"))
      (node (ref "U51") (pin "8") (pinfunction "DP_8") (pintype "input"))
    )
    (net (code "37") (name "GND") (class "Default")
      (node (ref "C459") (pin "1") (pinfunction "1_1") (pintype "passive"))
      (node (ref "C460") (pin "1") (pinfunction "1_1") (pintype "passive"))
      (node (ref "C461") (pin "1") (pinfunction "1_1") (pintype "passive"))
      (node (ref "C462") (pin "1") (pinfunction "1_1") (pintype "passive"))
      (node (ref "C463") (pin "1") (pinfunction "1_1") (pintype "passive"))
      (node (ref "C464") (pin "1") (pinfunction "1_1") (pintype "passive"))
      (node (ref "C465") (pin "1") (pinfunction "1_1") (pintype "passive"))
      (node (ref "C466") (pin "1") (pinfunction "1_1") (pintype "passive"))
      (node (ref "C467") (pin "1") (pinfunction "1_1") (pintype "passive"))
      (node (ref "C468") (pin "1") (pinfunction "1_1") (pintype "passive"))
      (node (ref "C469") (pin "1") (pinfunction "1_1") (pintype "passive"))
      (node (ref "C470") (pin "1") (pinfunction "1_1") (pintype "passive"))
      (node (ref "C471") (pin "1") (pinfunction "1_1") (pintype "passive"))
      (node (ref "C472") (pin "1") (pinfunction "1_1") (pintype "passive"))
      (node (ref "C473") (pin "1") (pinfunction "1_1") (pintype "passive"))
      (node (ref "C474") (pin "1") (pinfunction "1_1") (pintype "passive"))
      (node (ref "C475") (pin "1") (pinfunction "1_1") (pintype "passive"))
      (node (ref "C476") (pin "1") (pinfunction "1_1") (pintype "passive"))
      (node (ref "C477") (pin "1") (pinfunction "1_1") (pintype "passive"))
      (node (ref "C478") (pin "1") (pinfunction "1_1") (pintype "passive"))
      (node (ref "C479") (pin "1") (pinfunction "1_1") (pintype "passive"))
      (node (ref "C480") (pin "1") (pinfunction "1_1") (pintype "passive"))
      (node (ref "C481") (pin "1") (pinfunction "1_1") (pintype "passive"))
      (node (ref "C482") (pin "1") (pinfunction "1_1") (pintype "passive"))
      (node (ref "C483") (pin "1") (pinfunction "1_1") (pintype "passive"))
      (node (ref "C484") (pin "1") (pinfunction "1_1") (pintype "passive"))
      (node (ref "D29") (pin "G") (pinfunction "A_G") (pintype "passive"))
      (node (ref "J6") (pin "5") (pinfunction "GND_5") (pintype "power_in"))
      (node (ref "R286") (pin "2") (pinfunction "2_2") (pintype "passive"))
      (node (ref "R287") (pin "1") (pinfunction "1_1") (pintype "passive"))
      (node (ref "R292") (pin "1") (pinfunction "1_1") (pintype "passive"))
      (node (ref "R294") (pin "1") (pinfunction "1_1") (pintype "passive"))
      (node (ref "R295") (pin "1") (pinfunction "1_1") (pintype "passive"))
      (node (ref "R296") (pin "1") (pinfunction "1_1") (pintype "passive"))
      (node (ref "R298") (pin "2") (pinfunction "2_2") (pintype "passive"))
      (node (ref "R301") (pin "1") (pinfunction "1_1") (pintype "passive"))
      (node (ref "U21") (pin "3") (pinfunction "GND_3") (pintype "passive"))
      (node (ref "U49") (pin "7") (pinfunction "GND_7") (pintype "passive"))
      (node (ref "U50") (pin "2") (pinfunction "GND_2") (pintype "power_in"))
      (node (ref "U51") (pin "1") (pinfunction "GND_1") (pintype "power_in"))
      (node (ref "U51") (pin "10") (pinfunction "AGND_10") (pintype "power_in"))
      (node (ref "U51") (pin "11") (pinfunction "GND_11") (pintype "power_in"))
      (node (ref "U51") (pin "13") (pinfunction "TEST_13") (pintype "input"))
      (node (ref "U51") (pin "15") (pinfunction "GND_15") (pintype "power_in"))
      (node (ref "U51") (pin "25") (pinfunction "GND_25") (pintype "power_in"))
      (node (ref "U51") (pin "35") (pinfunction "GND_35") (pintype "power_in"))
      (node (ref "U51") (pin "47") (pinfunction "GND_47") (pintype "power_in"))
      (node (ref "U51") (pin "5") (pinfunction "GND_5") (pintype "power_in"))
      (node (ref "U51") (pin "51") (pinfunction "GND_51") (pintype "power_in"))
      (node (ref "U51") (pin "65") (pinfunction "GND_65") (pintype "power_in"))
      (node (ref "U52") (pin "4") (pinfunction "GND_4") (pintype "passive"))
      (node (ref "U53") (pin "2") (pinfunction "GND_2") (pintype "passive"))
      (node (ref "U55") (pin "2") (pinfunction "VSS_2") (pintype "power_in"))
    )
    (net (code "38") (name "Net-(J6-V)") (class "Default")
      (node (ref "J6") (pin "1") (pinfunction "V_1") (pintype "power_in"))
      (node (ref "R289") (pin "1") (pinfunction "1_1") (pintype "passive"))
    )
    (net (code "39") (name "Net-(R289-Pad2)") (class "Default")
      (node (ref "R289") (pin "2") (pinfunction "2_2") (pintype "passive"))
      (node (ref "R290") (pin "1") (pinfunction "1_1") (pintype "passive"))
      (node (ref "R294") (pin "2") (pinfunction "2_2") (pintype "passive"))
    )
    (net (code "40") (name "Net-(R304-Pad1)") (class "Default")
      (node (ref "R304") (pin "1") (pinfunction "1_1") (pintype "passive"))
      (node (ref "U21") (pin "4") (pintype "output"))
      (node (ref "U53") (pin "1") (pintype "passive"))
    )
    (net (code "41") (name "Net-(U50-OUT)") (class "Default")
      (node (ref "U50") (pin "3") (pinfunction "OUT_3") (pintype "output"))
      (node (ref "U51") (pin "2") (pinfunction "OSCI_2") (pintype "input"))
    )
    (net (code "42") (name "Net-(U51-ADBUS2)") (class "Default")
      (node (ref "R285") (pin "1") (pinfunction "1_1") (pintype "passive"))
      (node (ref "U51") (pin "18") (pinfunction "ADBUS2_18") (pintype "bidirectional"))
    )
    (net (code "43") (name "Net-(U51-BDBUS5)") (class "Default")
      (node (ref "R291") (pin "1") (pinfunction "1_1") (pintype "passive"))
      (node (ref "U51") (pin "32") (pinfunction "BDBUS5_32") (pintype "bidirectional"))
    )
    (net (code "44") (name "Net-(U51-REF)") (class "Default")
      (node (ref "R295") (pin "2") (pinfunction "2_2") (pintype "passive"))
      (node (ref "U51") (pin "6") (pinfunction "REF_6") (pintype "input"))
    )
    (net (code "45") (name "Net-(U51-RESET#)") (class "Default")
      (node (ref "R290") (pin "2") (pinfunction "2_2") (pintype "passive"))
      (node (ref "U51") (pin "14") (pinfunction "RESET#_14") (pintype "input"))
    )
    (net (code "46") (name "Net-(U55-D0)") (class "Default")
      (node (ref "R306") (pin "1") (pinfunction "1_1") (pintype "passive"))
      (node (ref "R309") (pin "1") (pinfunction "1_1") (pintype "passive"))
      (node (ref "U55") (pin "1") (pinfunction "D0_1") (pintype "output"))
    )
    (net (code "47") (name "SHIELD") (class "Default")
      (node (ref "J6") (pin "S1") (pinfunction "S1_S1") (pintype "power_in"))
      (node (ref "J6") (pin "S2") (pinfunction "S2_S2") (pintype "power_in"))
      (node (ref "J6") (pin "S3") (pinfunction "S3_S3") (pintype "power_in"))
      (node (ref "J6") (pin "S4") (pinfunction "S4_S4") (pintype "power_in"))
    )
    (net (code "48") (name "VCC1V8") (class "Default")
      (node (ref "C459") (pin "2") (pinfunction "2_2") (pintype "passive"))
      (node (ref "C460") (pin "2") (pinfunction "2_2") (pintype "passive"))
      (node (ref "C461") (pin "2") (pinfunction "2_2") (pintype "passive"))
      (node (ref "C470") (pin "2") (pinfunction "2_2") (pintype "passive"))
      (node (ref "U51") (pin "12") (pinfunction "VCORE_12") (pintype "power_in"))
      (node (ref "U51") (pin "37") (pinfunction "VCORE_37") (pintype "power_in"))
      (node (ref "U51") (pin "49") (pinfunction "VREGOUT_49") (pintype "power_in"))
      (node (ref "U51") (pin "64") (pinfunction "VCORE_64") (pintype "power_in"))
    )
    (net (code "49") (name "VCC3V3") (class "Default")
      (node (ref "C462") (pin "2") (pinfunction "2_2") (pintype "passive"))
      (node (ref "C463") (pin "2") (pinfunction "2_2") (pintype "passive"))
      (node (ref "C464") (pin "2") (pinfunction "2_2") (pintype "passive"))
      (node (ref "C465") (pin "2") (pinfunction "2_2") (pintype "passive"))
      (node (ref "C466") (pin "2") (pinfunction "2_2") (pintype "passive"))
      (node (ref "C467") (pin "2") (pinfunction "2_2") (pintype "passive"))
      (node (ref "C468") (pin "2") (pinfunction "2_2") (pintype "passive"))
      (node (ref "C469") (pin "2") (pinfunction "2_2") (pintype "passive"))
      (node (ref "C471") (pin "2") (pinfunction "2_2") (pintype "passive"))
      (node (ref "C472") (pin "2") (pinfunction "2_2") (pintype "passive"))
      (node (ref "C473") (pin "2") (pinfunction "2_2") (pintype "passive"))
      (node (ref "C474") (pin "2") (pinfunction "2_2") (pintype "passive"))
      (node (ref "C475") (pin "2") (pinfunction "2_2") (pintype "passive"))
      (node (ref "C476") (pin "2") (pinfunction "2_2") (pintype "passive"))
      (node (ref "FB27") (pin "1") (pinfunction "1_1") (pintype "passive"))
      (node (ref "FB28") (pin "1") (pinfunction "1_1") (pintype "passive"))
      (node (ref "R284") (pin "2") (pinfunction "2_2") (pintype "passive"))
      (node (ref "R288") (pin "2") (pinfunction "2_2") (pintype "passive"))
      (node (ref "R293") (pin "2") (pinfunction "2_2") (pintype "passive"))
      (node (ref "R297") (pin "2") (pinfunction "2_2") (pintype "passive"))
      (node (ref "R299") (pin "2") (pinfunction "2_2") (pintype "passive"))
      (node (ref "R300") (pin "2") (pinfunction "2_2") (pintype "passive"))
      (node (ref "R302") (pin "2") (pinfunction "2_2") (pintype "passive"))
      (node (ref "R303") (pin "2") (pinfunction "2_2") (pintype "passive"))
      (node (ref "R304") (pin "2") (pinfunction "2_2") (pintype "passive"))
      (node (ref "R305") (pin "2") (pinfunction "2_2") (pintype "passive"))
      (node (ref "R306") (pin "2") (pinfunction "2_2") (pintype "passive"))
      (node (ref "R307") (pin "2") (pinfunction "2_2") (pintype "passive"))
      (node (ref "R308") (pin "2") (pinfunction "2_2") (pintype "passive"))
      (node (ref "U21") (pin "5") (pinfunction "VCC_5") (pintype "passive"))
      (node (ref "U49") (pin "14") (pinfunction "VCC_14") (pintype "passive"))
      (node (ref "U50") (pin "4") (pinfunction "VCC_4") (pintype "power_in"))
      (node (ref "U51") (pin "20") (pinfunction "VCCIO_20") (pintype "power_in"))
      (node (ref "U51") (pin "31") (pinfunction "VCCIO_31") (pintype "power_in"))
      (node (ref "U51") (pin "42") (pinfunction "VCCIO_42") (pintype "power_in"))
      (node (ref "U51") (pin "50") (pinfunction "VREGIN_50") (pintype "power_in"))
      (node (ref "U51") (pin "56") (pinfunction "VCCIO_56") (pintype "power_in"))
      (node (ref "U52") (pin "8") (pinfunction "VCC_8") (pintype "power_in"))
      (node (ref "U53") (pin "5") (pinfunction "VCC_5") (pintype "passive"))
      (node (ref "U55") (pin "6") (pinfunction "VCC_6") (pintype "power_in"))
    )
    (net (code "50") (name "unconnected-(D29A-K-Pad1)") (class "Default")
      (node (ref "D29") (pin "1") (pinfunction "K_1") (pintype "passive+no_connect"))
    )
    (net (code "51") (name "unconnected-(D29D-K-Pad4)") (class "Default")
      (node (ref "D29") (pin "4") (pinfunction "K_4") (pintype "passive+no_connect"))
    )
    (net (code "52") (name "unconnected-(J6-ID-Pad4)") (class "Default")
      (node (ref "J6") (pin "4") (pinfunction "ID_4") (pintype "bidirectional+no_connect"))
    )
    (net (code "53") (name "unconnected-(U50-E_D-Pad1)") (class "Default")
      (node (ref "U50") (pin "1") (pinfunction "E_D_1") (pintype "input+no_connect"))
    )
    (net (code "54") (name "unconnected-(U51-ADBUS6-Pad23)") (class "Default")
      (node (ref "U51") (pin "23") (pinfunction "ADBUS6_23") (pintype "bidirectional"))
    )
    (net (code "55") (name "unconnected-(U51-ADBUS7-Pad24)") (class "Default")
      (node (ref "U51") (pin "24") (pinfunction "ADBUS7_24") (pintype "bidirectional"))
    )
    (net (code "56") (name "unconnected-(U51-BDBUS3-Pad29)") (class "Default")
      (node (ref "U51") (pin "29") (pinfunction "BDBUS3_29") (pintype "bidirectional"))
    )
    (net (code "57") (name "unconnected-(U51-BDBUS4-Pad30)") (class "Default")
      (node (ref "U51") (pin "30") (pinfunction "BDBUS4_30") (pintype "bidirectional"))
    )
    (net (code "58") (name "unconnected-(U51-BDBUS6-Pad33)") (class "Default")
      (node (ref "U51") (pin "33") (pinfunction "BDBUS6_33") (pintype "bidirectional"))
    )
    (net (code "59") (name "unconnected-(U51-BDBUS7-Pad34)") (class "Default")
      (node (ref "U51") (pin "34") (pinfunction "BDBUS7_34") (pintype "bidirectional"))
    )
    (net (code "60") (name "unconnected-(U51-CDBUS2-Pad40)") (class "Default")
      (node (ref "U51") (pin "40") (pinfunction "CDBUS2_40") (pintype "bidirectional"))
    )
    (net (code "61") (name "unconnected-(U51-CDBUS3-Pad41)") (class "Default")
      (node (ref "U51") (pin "41") (pinfunction "CDBUS3_41") (pintype "bidirectional"))
    )
    (net (code "62") (name "unconnected-(U51-CDBUS4-Pad43)") (class "Default")
      (node (ref "U51") (pin "43") (pinfunction "CDBUS4_43") (pintype "bidirectional"))
    )
    (net (code "63") (name "unconnected-(U51-CDBUS5-Pad44)") (class "Default")
      (node (ref "U51") (pin "44") (pinfunction "CDBUS5_44") (pintype "bidirectional"))
    )
    (net (code "64") (name "unconnected-(U51-CDBUS6-Pad45)") (class "Default")
      (node (ref "U51") (pin "45") (pinfunction "CDBUS6_45") (pintype "bidirectional"))
    )
    (net (code "65") (name "unconnected-(U51-CDBUS7-Pad46)") (class "Default")
      (node (ref "U51") (pin "46") (pinfunction "CDBUS7_46") (pintype "bidirectional"))
    )
    (net (code "66") (name "unconnected-(U51-DDBUS2-Pad53)") (class "Default")
      (node (ref "U51") (pin "53") (pinfunction "DDBUS2_53") (pintype "bidirectional"))
    )
    (net (code "67") (name "unconnected-(U51-DDBUS3-Pad54)") (class "Default")
      (node (ref "U51") (pin "54") (pinfunction "DDBUS3_54") (pintype "bidirectional"))
    )
    (net (code "68") (name "unconnected-(U51-DDBUS4-Pad55)") (class "Default")
      (node (ref "U51") (pin "55") (pinfunction "DDBUS4_55") (pintype "bidirectional"))
    )
    (net (code "69") (name "unconnected-(U51-DDBUS5-Pad57)") (class "Default")
      (node (ref "U51") (pin "57") (pinfunction "DDBUS5_57") (pintype "bidirectional"))
    )
    (net (code "70") (name "unconnected-(U51-DDBUS6-Pad58)") (class "Default")
      (node (ref "U51") (pin "58") (pinfunction "DDBUS6_58") (pintype "bidirectional"))
    )
    (net (code "71") (name "unconnected-(U51-DDBUS7-Pad59)") (class "Default")
      (node (ref "U51") (pin "59") (pinfunction "DDBUS7_59") (pintype "bidirectional"))
    )
    (net (code "72") (name "unconnected-(U51-OSCO-Pad3)") (class "Default")
      (node (ref "U51") (pin "3") (pinfunction "OSCO_3") (pintype "output+no_connect"))
    )
    (net (code "73") (name "unconnected-(U51-PWREN#-Pad60)") (class "Default")
      (node (ref "U51") (pin "60") (pinfunction "PWREN#_60") (pintype "output"))
    )
    (net (code "74") (name "unconnected-(U51-SUSPEND#-Pad36)") (class "Default")
      (node (ref "U51") (pin "36") (pinfunction "SUSPEND#_36") (pintype "output"))
    )
    (net (code "75") (name "unconnected-(U52-NC-Pad1)") (class "Default")
      (node (ref "U52") (pin "1") (pinfunction "NC_1") (pintype "passive+no_connect"))
    )
  )
)
